# mSD-Bee_v11.net
KiCad netlist of a schematic drawn in EAGLE
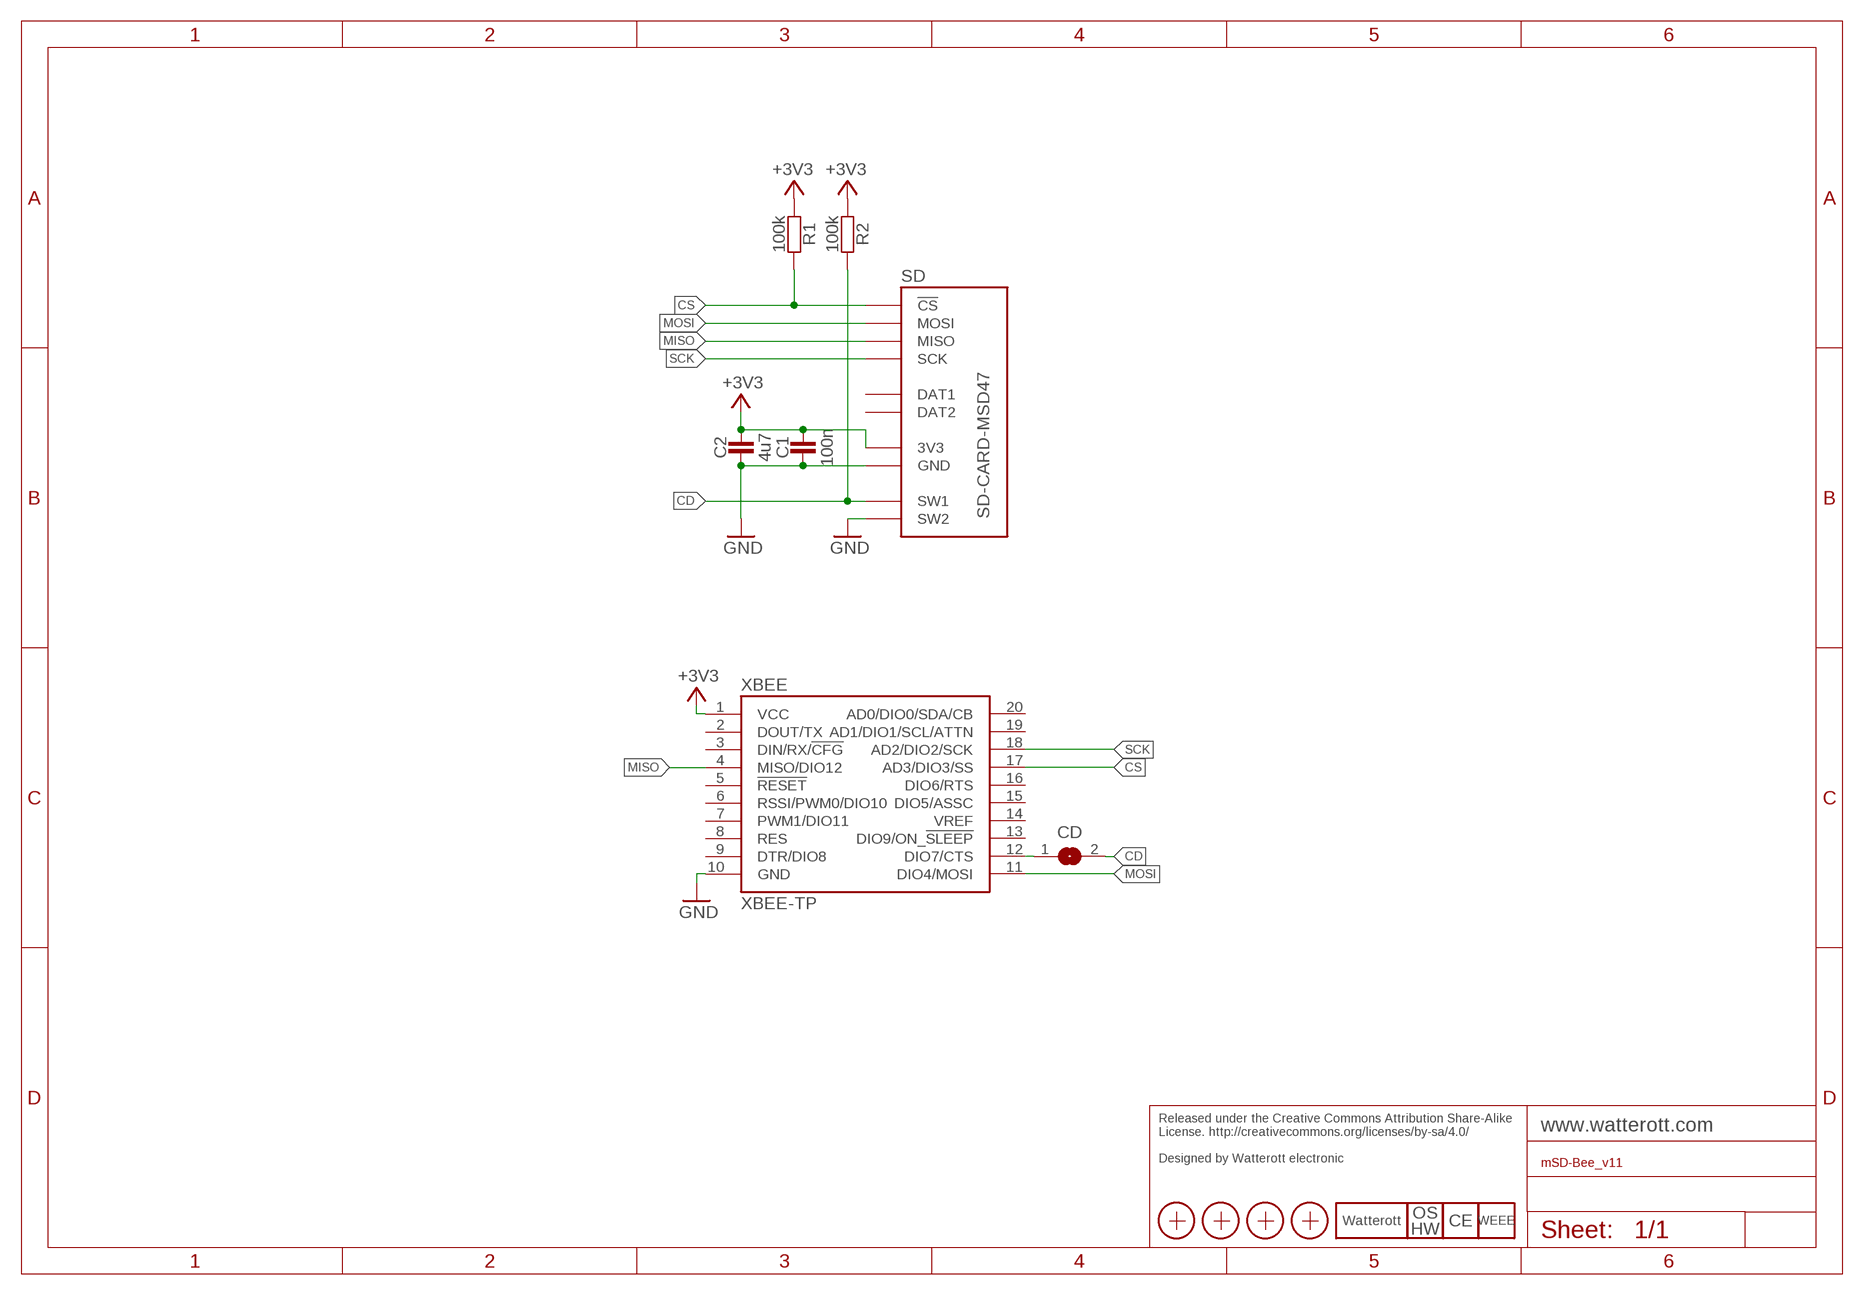
[diagram p0: schematic, sheet 1]

(export (version "E")
  (design (tool "Eeschema 10.0.6"))
  (components
    (comp (ref "C1")
      (value "100n")
      (footprint "eagle-import:C0402")
      (libsource (lib "eagle-import") (part "CAPACITOR-0402"))
    )
    (comp (ref "C2")
      (value "4u7")
      (footprint "eagle-import:C0603")
      (libsource (lib "eagle-import") (part "CAPACITOR-0603"))
    )
    (comp (ref "CD")
      (value "JUMPER2-0603")
      (footprint "eagle-import:JUMPER2-0603")
      (libsource (lib "eagle-import") (part "JUMPER2-0603"))
    )
    (comp (ref "LOGO3")
      (value "LOGO_SPARK-2")
      (footprint "eagle-import:SPARK_2MM")
      (libsource (lib "eagle-import") (part "LOGO_SPARK-2"))
    )
    (comp (ref "LOGO4")
      (value "LOGO_OSHW-2")
      (footprint "eagle-import:OSHW_2MM")
      (libsource (lib "eagle-import") (part "LOGO_OSHW-2"))
    )
    (comp (ref "LOGO5")
      (value "LOGO_CE-2")
      (footprint "eagle-import:CE_2MM")
      (libsource (lib "eagle-import") (part "LOGO_CE-2"))
    )
    (comp (ref "LOGO6")
      (value "LOGO_WEEE-4")
      (footprint "eagle-import:WEEE_4MM")
      (libsource (lib "eagle-import") (part "LOGO_WEEE-4"))
    )
    (comp (ref "R1")
      (value "100k")
      (footprint "eagle-import:C0402")
      (libsource (lib "eagle-import") (part "RESISTOR-0402"))
    )
    (comp (ref "R2")
      (value "100k")
      (footprint "eagle-import:C0402")
      (libsource (lib "eagle-import") (part "RESISTOR-0402"))
    )
    (comp (ref "SD")
      (value "SD-CARD-MSD47")
      (footprint "eagle-import:SD_47309XXXX")
      (libsource (lib "eagle-import") (part "SD-CARD-MSD47"))
    )
    (comp (ref "X1")
      (value "PASSER-07")
      (footprint "eagle-import:PASSER_07MM")
      (libsource (lib "eagle-import") (part "PASSER-07"))
    )
    (comp (ref "X2")
      (value "PASSER-07")
      (footprint "eagle-import:PASSER_07MM")
      (libsource (lib "eagle-import") (part "PASSER-07"))
    )
    (comp (ref "X3")
      (value "PASSER-07")
      (footprint "eagle-import:PASSER_07MM")
      (libsource (lib "eagle-import") (part "PASSER-07"))
    )
    (comp (ref "X4")
      (value "PASSER-07")
      (footprint "eagle-import:PASSER_07MM")
      (libsource (lib "eagle-import") (part "PASSER-07"))
    )
    (comp (ref "XBEE")
      (value "XBEE-TP")
      (footprint "eagle-import:XBEE_TP")
      (libsource (lib "eagle-import") (part "XBEE-TP"))
    )
  )
  (nets
    (net (code "1") (name "+3V3") (class "Default")
      (node (ref "C1") (pin "2") (pinfunction "2_2") (pintype "passive"))
      (node (ref "C2") (pin "2") (pinfunction "2_2") (pintype "passive"))
      (node (ref "R1") (pin "2") (pinfunction "2_2") (pintype "passive"))
      (node (ref "R2") (pin "2") (pinfunction "2_2") (pintype "passive"))
      (node (ref "SD") (pin "VCC") (pinfunction "3V3_VCC") (pintype "bidirectional"))
      (node (ref "XBEE") (pin "1") (pinfunction "VCC_1") (pintype "power_in"))
    )
    (net (code "2") (name "CD") (class "Default")
      (node (ref "CD") (pin "2") (pinfunction "2_2") (pintype "passive"))
      (node (ref "R2") (pin "1") (pinfunction "1_1") (pintype "passive"))
      (node (ref "SD") (pin "SW1") (pinfunction "SW1_SW1") (pintype "bidirectional"))
    )
    (net (code "3") (name "CS") (class "Default")
      (node (ref "R1") (pin "1") (pinfunction "1_1") (pintype "passive"))
      (node (ref "SD") (pin "CS") (pinfunction "~{CS}_CS") (pintype "bidirectional"))
      (node (ref "XBEE") (pin "17") (pinfunction "AD3/DIO3/SS_17") (pintype "bidirectional"))
    )
    (net (code "4") (name "GND") (class "Default")
      (node (ref "C1") (pin "1") (pinfunction "1_1") (pintype "passive"))
      (node (ref "C2") (pin "1") (pinfunction "1_1") (pintype "passive"))
      (node (ref "SD") (pin "GND") (pinfunction "GND_GND") (pintype "bidirectional"))
      (node (ref "SD") (pin "GND@1") (pinfunction "GND_GND@1") (pintype "bidirectional"))
      (node (ref "SD") (pin "GND@2") (pinfunction "GND_GND@2") (pintype "bidirectional"))
      (node (ref "SD") (pin "SW2") (pinfunction "SW2_SW2") (pintype "bidirectional"))
      (node (ref "XBEE") (pin "10") (pinfunction "GND_10") (pintype "power_in"))
    )
    (net (code "5") (name "MISO") (class "Default")
      (node (ref "SD") (pin "MISO") (pinfunction "MISO_MISO") (pintype "bidirectional"))
      (node (ref "XBEE") (pin "4") (pinfunction "MISO/DIO12_4") (pintype "bidirectional"))
    )
    (net (code "6") (name "MOSI") (class "Default")
      (node (ref "SD") (pin "MOSI") (pinfunction "MOSI_MOSI") (pintype "bidirectional"))
      (node (ref "XBEE") (pin "11") (pinfunction "DIO4/MOSI_11") (pintype "bidirectional"))
    )
    (net (code "7") (name "Net-(XBEE-DIO7{slash}CTS)") (class "Default")
      (node (ref "CD") (pin "1") (pinfunction "1_1") (pintype "passive"))
      (node (ref "XBEE") (pin "12") (pinfunction "DIO7/CTS_12") (pintype "bidirectional"))
    )
    (net (code "8") (name "SCK") (class "Default")
      (node (ref "SD") (pin "SCK") (pinfunction "SCK_SCK") (pintype "bidirectional"))
      (node (ref "XBEE") (pin "18") (pinfunction "AD2/DIO2/SCK_18") (pintype "bidirectional"))
    )
    (net (code "9") (name "unconnected-(SD-PadDAT1)") (class "Default")
      (node (ref "SD") (pin "DAT1") (pinfunction "DAT1_DAT1") (pintype "bidirectional"))
    )
    (net (code "10") (name "unconnected-(SD-PadDAT2)") (class "Default")
      (node (ref "SD") (pin "DAT2") (pinfunction "DAT2_DAT2") (pintype "bidirectional"))
    )
    (net (code "11") (name "unconnected-(XBEE-AD0{slash}DIO0{slash}SDA{slash}CB-Pad20)") (class "Default")
      (node (ref "XBEE") (pin "20") (pinfunction "AD0/DIO0/SDA/CB_20") (pintype "bidirectional"))
    )
    (net (code "12") (name "unconnected-(XBEE-AD1{slash}DIO1{slash}SCL{slash}ATTN-Pad19)") (class "Default")
      (node (ref "XBEE") (pin "19") (pinfunction "AD1/DIO1/SCL/ATTN_19") (pintype "bidirectional"))
    )
    (net (code "13") (name "unconnected-(XBEE-DIN{slash}RX{slash}~{CFG}-Pad3)") (class "Default")
      (node (ref "XBEE") (pin "3") (pinfunction "DIN/RX/~{CFG}_3") (pintype "bidirectional"))
    )
    (net (code "14") (name "unconnected-(XBEE-DIO5{slash}ASSC-Pad15)") (class "Default")
      (node (ref "XBEE") (pin "15") (pinfunction "DIO5/ASSC_15") (pintype "bidirectional"))
    )
    (net (code "15") (name "unconnected-(XBEE-DIO6{slash}RTS-Pad16)") (class "Default")
      (node (ref "XBEE") (pin "16") (pinfunction "DIO6/RTS_16") (pintype "bidirectional"))
    )
    (net (code "16") (name "unconnected-(XBEE-DIO9{slash}ON_~{SLEEP}-Pad13)") (class "Default")
      (node (ref "XBEE") (pin "13") (pinfunction "DIO9/ON_~{SLEEP}_13") (pintype "bidirectional"))
    )
    (net (code "17") (name "unconnected-(XBEE-DOUT{slash}TX-Pad2)") (class "Default")
      (node (ref "XBEE") (pin "2") (pinfunction "DOUT/TX_2") (pintype "bidirectional"))
    )
    (net (code "18") (name "unconnected-(XBEE-DTR{slash}DIO8-Pad9)") (class "Default")
      (node (ref "XBEE") (pin "9") (pinfunction "DTR/DIO8_9") (pintype "bidirectional"))
    )
    (net (code "19") (name "unconnected-(XBEE-PWM1{slash}DIO11-Pad7)") (class "Default")
      (node (ref "XBEE") (pin "7") (pinfunction "PWM1/DIO11_7") (pintype "bidirectional"))
    )
    (net (code "20") (name "unconnected-(XBEE-RES-Pad8)") (class "Default")
      (node (ref "XBEE") (pin "8") (pinfunction "RES_8") (pintype "bidirectional"))
    )
    (net (code "21") (name "unconnected-(XBEE-RSSI{slash}PWM0{slash}DIO10-Pad6)") (class "Default")
      (node (ref "XBEE") (pin "6") (pinfunction "RSSI/PWM0/DIO10_6") (pintype "bidirectional"))
    )
    (net (code "22") (name "unconnected-(XBEE-VREF-Pad14)") (class "Default")
      (node (ref "XBEE") (pin "14") (pinfunction "VREF_14") (pintype "bidirectional"))
    )
    (net (code "23") (name "unconnected-(XBEE-~{RESET}-Pad5)") (class "Default")
      (node (ref "XBEE") (pin "5") (pinfunction "~{RESET}_5") (pintype "bidirectional"))
    )
  )
)
